# M_dulo_Ribatski_v_1_0.net
KiCad netlist of a schematic drawn in EAGLE
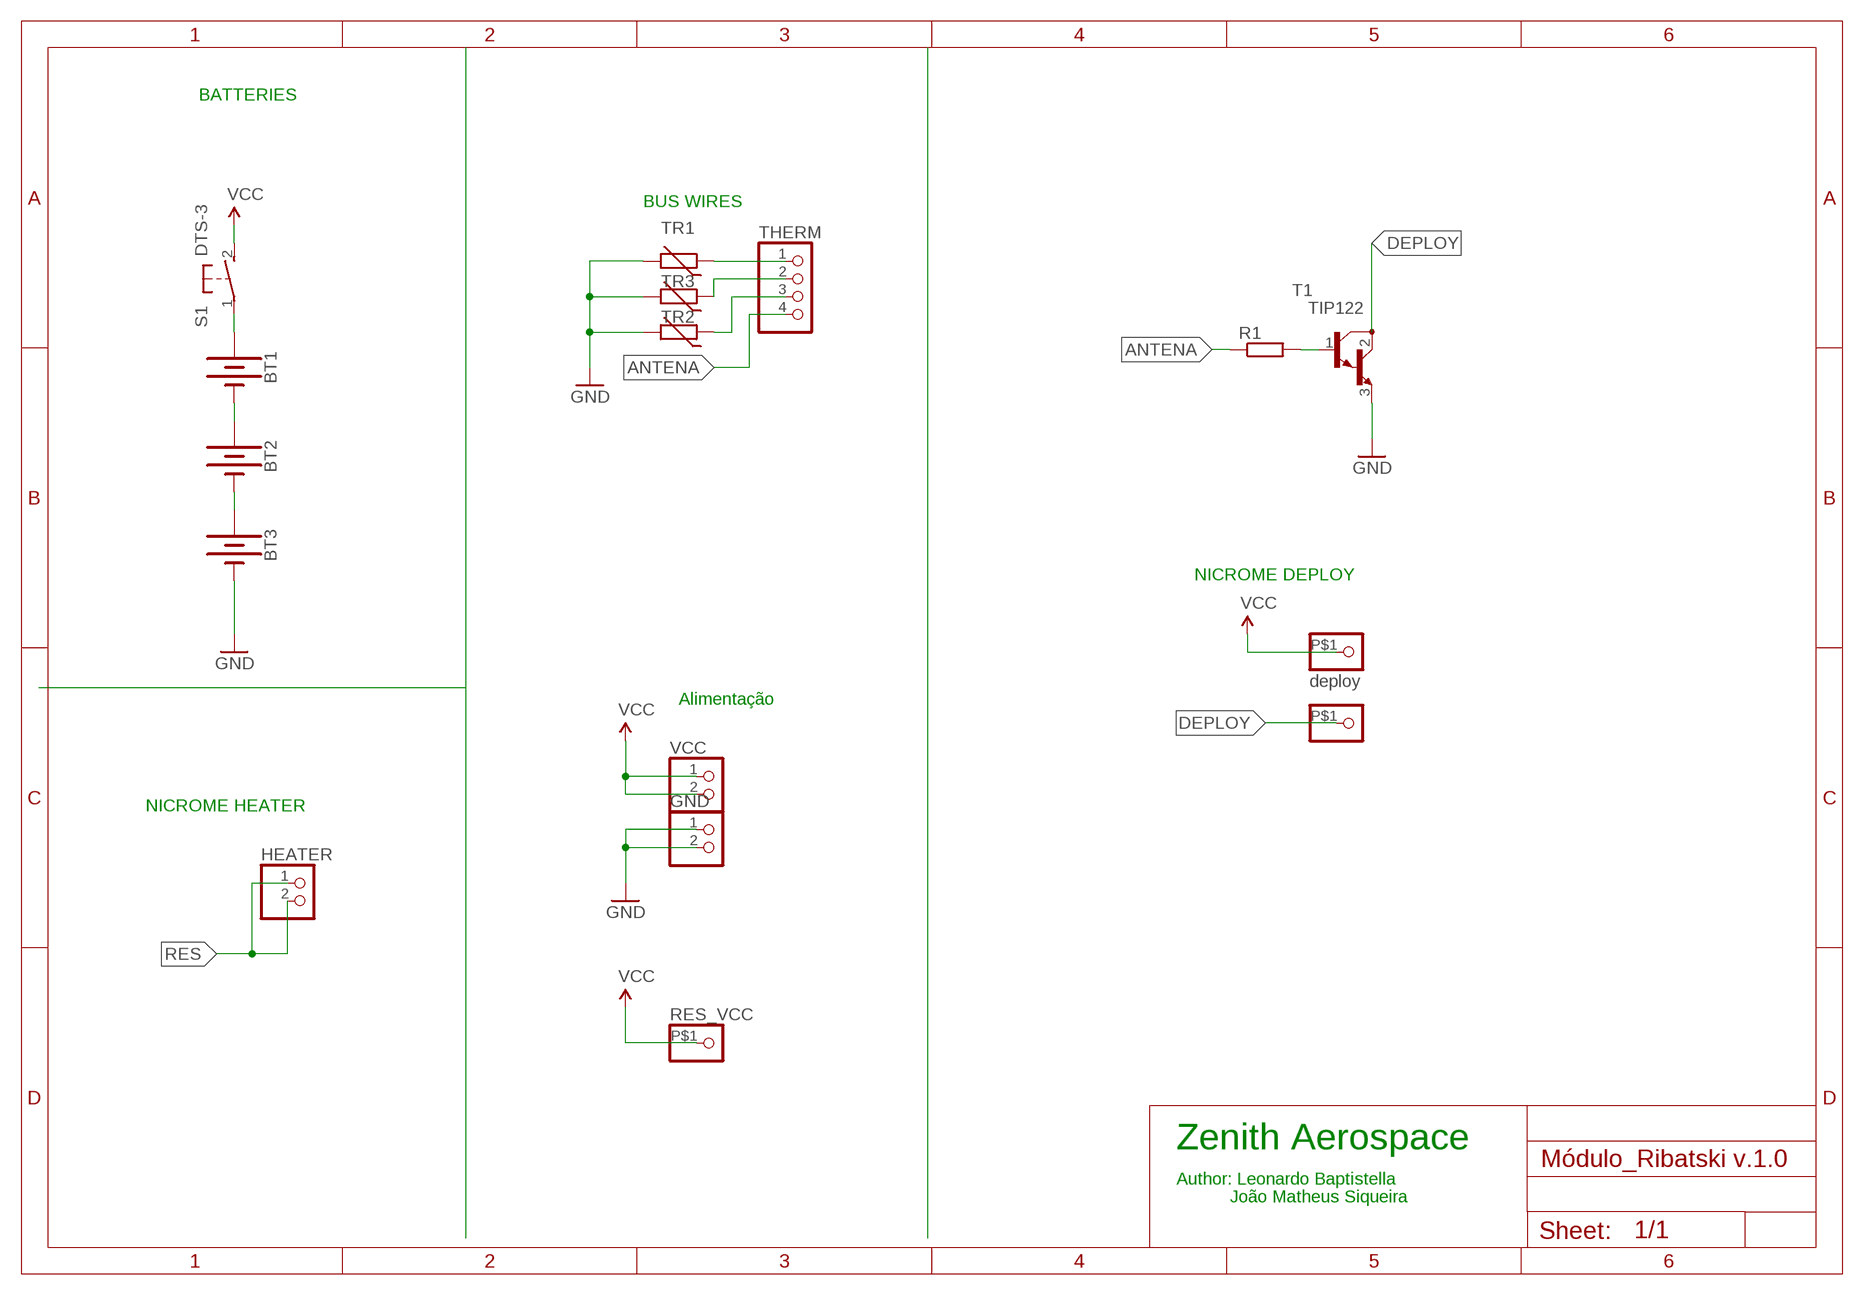
[diagram p0: schematic, sheet 1]

(export (version "E")
  (design (tool "Eeschema 10.0.6"))
  (components
    (comp (ref "BT1")
      (value "BATTERY-18650")
      (footprint "eagle-import:BATTERY_18650-HOLDER")
      (libsource (lib "eagle-import") (part "BATTERY-18650"))
    )
    (comp (ref "BT2")
      (value "BATTERY-18650")
      (footprint "eagle-import:BATTERY_18650-HOLDER")
      (libsource (lib "eagle-import") (part "BATTERY-18650"))
    )
    (comp (ref "BT3")
      (value "BATTERY-18650")
      (footprint "eagle-import:BATTERY_18650-HOLDER")
      (libsource (lib "eagle-import") (part "BATTERY-18650"))
    )
    (comp (ref "DEPLOY_GND")
      (value "PINHD-1X1-BIGPOGO")
      (footprint "eagle-import:1X1-BIGPOGO")
      (libsource (lib "eagle-import") (part "PINHD-1X1-BIGPOGO"))
    )
    (comp (ref "DEPLOY_VCC")
      (value "deploy")
      (footprint "eagle-import:1X1-BIGPOGO")
      (libsource (lib "eagle-import") (part "PINHD-1X1-BIGPOGO"))
    )
    (comp (ref "GND")
      (value "PINHD-1X2")
      (footprint "eagle-import:1X02")
      (libsource (lib "eagle-import") (part "PINHD-1X2"))
    )
    (comp (ref "HEATER")
      (value "PINHD-1X2")
      (footprint "eagle-import:1X02")
      (libsource (lib "eagle-import") (part "PINHD-1X2"))
    )
    (comp (ref "R1")
      (value "R-EU_R1206")
      (footprint "eagle-import:R1206")
      (libsource (lib "eagle-import") (part "R-EU_R1206"))
    )
    (comp (ref "RES_VCC")
      (value "PINHD-1X1-BIGPOGO")
      (footprint "eagle-import:1X1-BIGPOGO")
      (libsource (lib "eagle-import") (part "PINHD-1X1-BIGPOGO"))
    )
    (comp (ref "S1")
      (value "DTS-3")
      (footprint "eagle-import:DTS-3")
      (libsource (lib "eagle-import") (part "DTS-3"))
    )
    (comp (ref "T1")
      (value "TIP122")
      (footprint "eagle-import:TO220")
      (libsource (lib "eagle-import") (part "TIP122"))
    )
    (comp (ref "THERM")
      (value "HEADER-1X4")
      (footprint "eagle-import:1X04_OVAL")
      (libsource (lib "eagle-import") (part "HEADER-1X4"))
    )
    (comp (ref "TR1")
      (value "THERMISTOR_R-5")
      (footprint "eagle-import:R-5")
      (libsource (lib "eagle-import") (part "THERMISTOR_R-5"))
    )
    (comp (ref "TR2")
      (value "THERMISTOR_R-5")
      (footprint "eagle-import:R-5")
      (libsource (lib "eagle-import") (part "THERMISTOR_R-5"))
    )
    (comp (ref "TR3")
      (value "THERMISTOR_R-5")
      (footprint "eagle-import:R-5")
      (libsource (lib "eagle-import") (part "THERMISTOR_R-5"))
    )
    (comp (ref "VCC")
      (value "PINHD-1X2")
      (footprint "eagle-import:1X02")
      (libsource (lib "eagle-import") (part "PINHD-1X2"))
    )
  )
  (nets
    (net (code "1") (name "ANTENA") (class "Default")
      (node (ref "R1") (pin "1") (pinfunction "1_1") (pintype "passive"))
      (node (ref "THERM") (pin "4") (pinfunction "4_4") (pintype "passive"))
    )
    (net (code "2") (name "DEPLOY") (class "Default")
      (node (ref "DEPLOY_GND") (pin "P$1") (pinfunction "1_P$1") (pintype "passive"))
      (node (ref "T1") (pin "2") (pinfunction "C_2") (pintype "passive"))
    )
    (net (code "3") (name "GND") (class "Default")
      (node (ref "BT3") (pin "GND@1") (pinfunction "-_GND@1") (pintype "power_in"))
      (node (ref "GND") (pin "1") (pinfunction "1_1") (pintype "passive"))
      (node (ref "GND") (pin "2") (pinfunction "2_2") (pintype "passive"))
      (node (ref "T1") (pin "3") (pinfunction "E_3") (pintype "passive"))
      (node (ref "TR1") (pin "2") (pinfunction "2_2") (pintype "passive"))
      (node (ref "TR2") (pin "2") (pinfunction "2_2") (pintype "passive"))
      (node (ref "TR3") (pin "2") (pinfunction "2_2") (pintype "passive"))
    )
    (net (code "4") (name "Net-(BT1-+)") (class "Default")
      (node (ref "BT1") (pin "PWR@1") (pinfunction "+_PWR@1") (pintype "power_in"))
      (node (ref "S1") (pin "1") (pinfunction "1_1") (pintype "passive"))
    )
    (net (code "5") (name "Net-(BT1--)") (class "Default")
      (node (ref "BT1") (pin "GND@1") (pinfunction "-_GND@1") (pintype "power_in"))
      (node (ref "BT2") (pin "PWR@1") (pinfunction "+_PWR@1") (pintype "power_in"))
    )
    (net (code "6") (name "Net-(BT2--)") (class "Default")
      (node (ref "BT2") (pin "GND@1") (pinfunction "-_GND@1") (pintype "power_in"))
      (node (ref "BT3") (pin "PWR@1") (pinfunction "+_PWR@1") (pintype "power_in"))
    )
    (net (code "7") (name "Net-(T1-B)") (class "Default")
      (node (ref "R1") (pin "2") (pinfunction "2_2") (pintype "passive"))
      (node (ref "T1") (pin "1") (pinfunction "B_1") (pintype "passive"))
    )
    (net (code "8") (name "Net-(THERM-Pad1)") (class "Default")
      (node (ref "THERM") (pin "1") (pinfunction "1_1") (pintype "passive"))
      (node (ref "TR1") (pin "1") (pinfunction "1_1") (pintype "passive"))
    )
    (net (code "9") (name "Net-(THERM-Pad2)") (class "Default")
      (node (ref "THERM") (pin "2") (pinfunction "2_2") (pintype "passive"))
      (node (ref "TR3") (pin "1") (pinfunction "1_1") (pintype "passive"))
    )
    (net (code "10") (name "Net-(THERM-Pad3)") (class "Default")
      (node (ref "THERM") (pin "3") (pinfunction "3_3") (pintype "passive"))
      (node (ref "TR2") (pin "1") (pinfunction "1_1") (pintype "passive"))
    )
    (net (code "11") (name "RES") (class "Default")
      (node (ref "HEATER") (pin "1") (pinfunction "1_1") (pintype "passive"))
      (node (ref "HEATER") (pin "2") (pinfunction "2_2") (pintype "passive"))
    )
    (net (code "12") (name "VCC") (class "Default")
      (node (ref "DEPLOY_VCC") (pin "P$1") (pinfunction "1_P$1") (pintype "passive"))
      (node (ref "RES_VCC") (pin "P$1") (pinfunction "1_P$1") (pintype "passive"))
      (node (ref "S1") (pin "2") (pinfunction "2_2") (pintype "passive"))
      (node (ref "VCC") (pin "1") (pinfunction "1_1") (pintype "passive"))
      (node (ref "VCC") (pin "2") (pinfunction "2_2") (pintype "passive"))
    )
  )
)
